# MachChoCaAn.net
KiCad netlist of a schematic drawn in Altium Designer
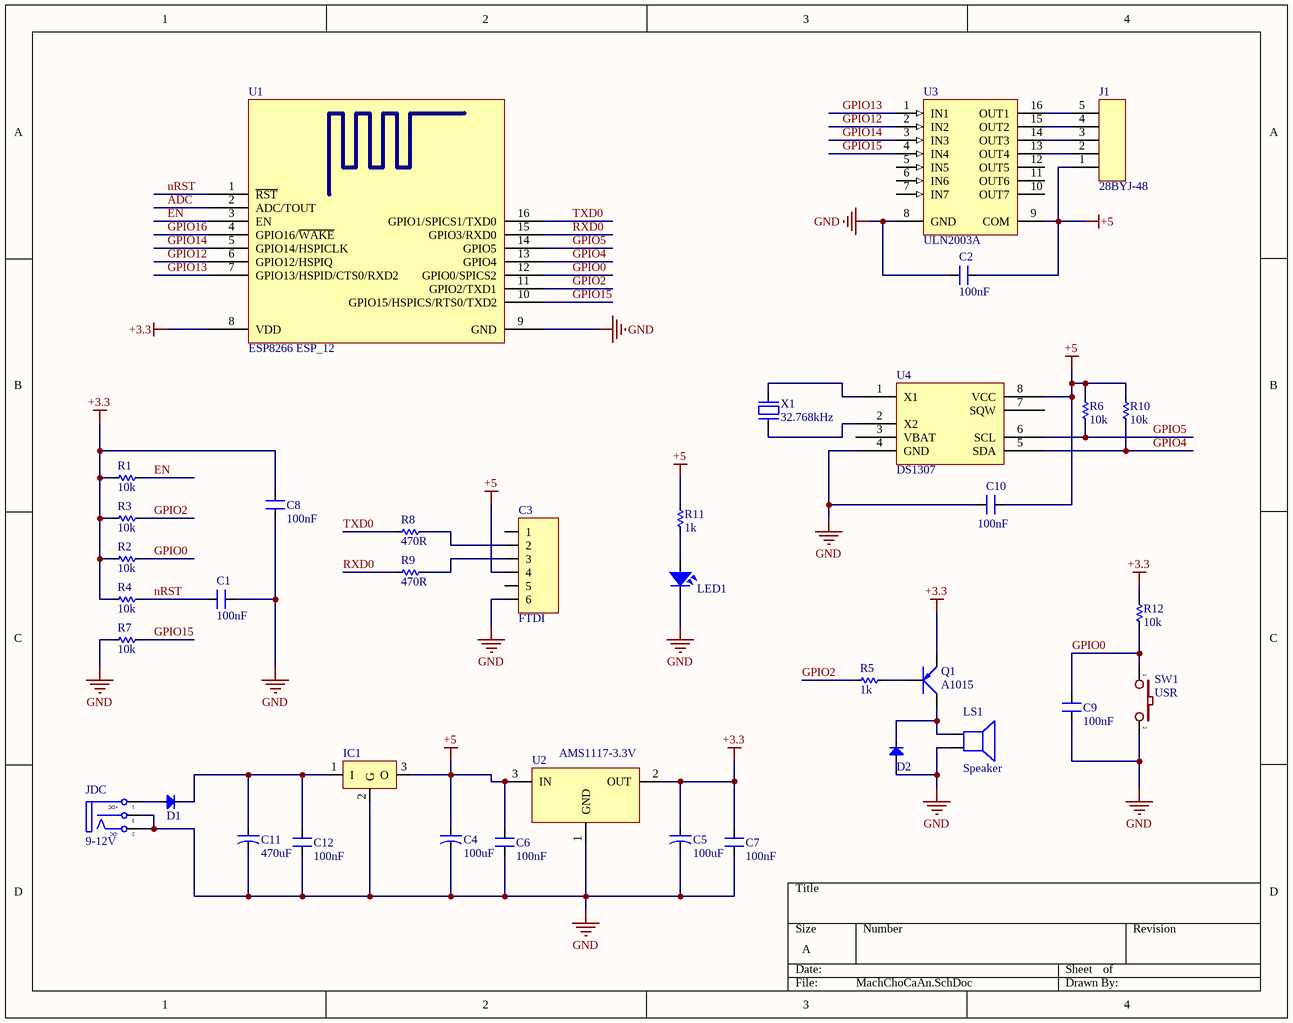
[diagram p0: MachChoCaAn.SchDoc]

(export (version "E")
  (design (tool "Eeschema 10.0.6"))
  (components
    (comp (ref "C1") (value "100nF") (footprint "CN-SMD-0805") (libsource (lib "LIBRARY") (part "CN")))
    (comp (ref "C2") (value "100nF") (footprint "CN-SMD-0805") (libsource (lib "LIBRARY") (part "CN")))
    (comp (ref "C3")
      (value "FTDI")
      (footprint "JP6-D1T")
      (description "WR-PHD 2.54 mm Angled Socket Header")
      (fields
        (field (name "MANUFACTURER") "Würth Elektronik eiSos GmbH")
        (field (name "PARTNO") "613006143121")
        (field (name "CREATED BY") "Karrer Zheng")
      )
      (libsource (lib "LIBRARY") (part "JP6"))
    )
    (comp (ref "C4")
      (value "100uF")
      (footprint "CA-ALU-6.3")
      (description "Capacitor (Semiconductor SIM Model)")
      (fields (field (name "PUBLISHER") "Altium Limited"))
      (libsource (lib "LIBRARY") (part "CN-ALU-DIP"))
    )
    (comp (ref "C5")
      (value "100uF")
      (footprint "CA-ALU-6.3")
      (description "Capacitor (Semiconductor SIM Model)")
      (fields (field (name "PUBLISHER") "Altium Limited"))
      (libsource (lib "LIBRARY") (part "CN-ALU-DIP"))
    )
    (comp (ref "C6") (value "100nF") (footprint "CN-SMD-0805") (libsource (lib "LIBRARY") (part "CN")))
    (comp (ref "C7") (value "100nF") (footprint "CN-SMD-0805") (libsource (lib "LIBRARY") (part "CN")))
    (comp (ref "C8") (value "100nF") (footprint "CN-SMD-0805") (libsource (lib "LIBRARY") (part "CN")))
    (comp (ref "C9") (value "100nF") (footprint "CN-SMD-0805") (libsource (lib "LIBRARY") (part "CN")))
    (comp (ref "C10") (value "100nF") (footprint "CN-SMD-0805") (libsource (lib "LIBRARY") (part "CN")))
    (comp (ref "C11")
      (value "470uF")
      (footprint "CA-ALU-10RL")
      (description "Capacitor (Semiconductor SIM Model)")
      (fields (field (name "PUBLISHER") "Altium Limited"))
      (libsource (lib "LIBRARY") (part "CN-ALU-DIP"))
    )
    (comp (ref "C12") (value "100nF") (footprint "CN-SMD-0805") (libsource (lib "LIBRARY") (part "CN")))
    (comp (ref "D1")
      (value "Diode SMD")
      (footprint "DIO-SMD-106")
      (description "Default Diode")
      (fields (field (name "PUBLISHER") "Altium Limited"))
      (libsource (lib "LIBRARY") (part "Diode SMD"))
    )
    (comp (ref "D2")
      (value "Diode SMD")
      (footprint "DIO-SMD-106")
      (description "Default Diode")
      (fields (field (name "PUBLISHER") "Altium Limited"))
      (libsource (lib "LIBRARY") (part "Diode SMD"))
    )
    (comp (ref "IC1")
      (value "LM78xx")
      (footprint "TO252-123")
      (description "Positive Voltage Regulator")
      (fields (field (name "PUBLISHER") "Altium Limited"))
      (libsource (lib "LIBRARY") (part "LM78xx"))
    )
    (comp (ref "J1") (value "28BYJ-48") (footprint "XH2.54-5P") (libsource (lib "User") (part "XH2.54-5P")))
    (comp (ref "JDC")
      (value "9-12V")
      (footprint "DC0")
      (description "Jac DC input")
      (libsource (lib "LIBRARY") (part "DCIN"))
    )
    (comp (ref "LED1")
      (value "PWR")
      (footprint "LED-0805-Orange")
      (libsource (lib "LIBRARY") (part "LED SMD"))
    )
    (comp (ref "LS1")
      (value "Speaker")
      (footprint "SPEAKER")
      (description "Loudspeaker")
      (fields (field (name "PUBLISHER") "Altium Limited"))
      (libsource (lib "LIBRARY") (part "Speaker"))
    )
    (comp (ref "Q1")
      (value "A1015")
      (footprint "SOT23B")
      (description "Dán")
      (libsource (lib "THU VIEN SCH_04042017_1") (part "A1015"))
    )
    (comp (ref "R1")
      (value "10k")
      (footprint "RES-SMD-0805")
      (description "Resistor")
      (fields
        (field (name "MANUFACTURER") "Generic Components")
        (field (name "PUBLISHER") "Altium Hobart Technology Centre")
      )
      (libsource (lib "LIBRARY") (part "Res-SMD"))
    )
    (comp (ref "R2")
      (value "10k")
      (footprint "RES-SMD-0805")
      (description "Resistor")
      (fields
        (field (name "MANUFACTURER") "Generic Components")
        (field (name "PUBLISHER") "Altium Hobart Technology Centre")
      )
      (libsource (lib "LIBRARY") (part "Res-SMD"))
    )
    (comp (ref "R3")
      (value "10k")
      (footprint "RES-SMD-0805")
      (description "Resistor")
      (fields
        (field (name "MANUFACTURER") "Generic Components")
        (field (name "PUBLISHER") "Altium Hobart Technology Centre")
      )
      (libsource (lib "LIBRARY") (part "Res-SMD"))
    )
    (comp (ref "R4")
      (value "10k")
      (footprint "RES-SMD-0805")
      (description "Resistor")
      (fields
        (field (name "MANUFACTURER") "Generic Components")
        (field (name "PUBLISHER") "Altium Hobart Technology Centre")
      )
      (libsource (lib "LIBRARY") (part "Res-SMD"))
    )
    (comp (ref "R5")
      (value "1k")
      (footprint "RES-SMD-0805")
      (description "Resistor")
      (fields
        (field (name "MANUFACTURER") "Generic Components")
        (field (name "PUBLISHER") "Altium Hobart Technology Centre")
      )
      (libsource (lib "LIBRARY") (part "Res-SMD"))
    )
    (comp (ref "R6")
      (value "10k")
      (footprint "RES-SMD-0805")
      (description "Resistor")
      (fields
        (field (name "MANUFACTURER") "Generic Components")
        (field (name "PUBLISHER") "Altium Hobart Technology Centre")
      )
      (libsource (lib "LIBRARY") (part "Res-SMD"))
    )
    (comp (ref "R7")
      (value "10k")
      (footprint "RES-SMD-0805")
      (description "Resistor")
      (fields
        (field (name "MANUFACTURER") "Generic Components")
        (field (name "PUBLISHER") "Altium Hobart Technology Centre")
      )
      (libsource (lib "LIBRARY") (part "Res-SMD"))
    )
    (comp (ref "R8")
      (value "470R")
      (footprint "RES-SMD-0805")
      (description "Resistor")
      (fields
        (field (name "MANUFACTURER") "Generic Components")
        (field (name "PUBLISHER") "Altium Hobart Technology Centre")
      )
      (libsource (lib "LIBRARY") (part "Res-SMD"))
    )
    (comp (ref "R9")
      (value "470R")
      (footprint "RES-SMD-0805")
      (description "Resistor")
      (fields
        (field (name "MANUFACTURER") "Generic Components")
        (field (name "PUBLISHER") "Altium Hobart Technology Centre")
      )
      (libsource (lib "LIBRARY") (part "Res-SMD"))
    )
    (comp (ref "R10")
      (value "10k")
      (footprint "RES-SMD-0805")
      (description "Resistor")
      (fields
        (field (name "MANUFACTURER") "Generic Components")
        (field (name "PUBLISHER") "Altium Hobart Technology Centre")
      )
      (libsource (lib "LIBRARY") (part "Res-SMD"))
    )
    (comp (ref "R11")
      (value "1k")
      (footprint "RES-SMD-0805")
      (description "Resistor")
      (fields
        (field (name "MANUFACTURER") "Generic Components")
        (field (name "PUBLISHER") "Altium Hobart Technology Centre")
      )
      (libsource (lib "LIBRARY") (part "Res-SMD"))
    )
    (comp (ref "R12")
      (value "10k")
      (footprint "RES-SMD-0805")
      (description "Resistor")
      (fields
        (field (name "MANUFACTURER") "Generic Components")
        (field (name "PUBLISHER") "Altium Hobart Technology Centre")
      )
      (libsource (lib "LIBRARY") (part "Res-SMD"))
    )
    (comp (ref "SW1")
      (value "USR")
      (footprint "SW1-DIP")
      (description "Switch button 2 pin")
      (libsource (lib "LIBRARY") (part "SW2"))
    )
    (comp (ref "U1")
      (value "ESP8266 ESP_12")
      (footprint "ESP8266 ESP_12")
      (description "ESP8266 ESP-12")
      (fields (field (name "PUBLISHER") "Cynetik Group") (field (name "LATESTREVIEWER") "Zion Blue"))
      (libsource (lib "ESP8266") (part "ESP8266 ESP_12"))
    )
    (comp (ref "U2")
      (value "AMS1117-3.3V")
      (footprint "SOT223")
      (description "800mA Low-Dropout Linear Regulator")
      (fields (field (name "CREATOR") "Nguyen Ba Bien"))
      (libsource (lib "LIBRARY") (part "LM1117"))
    )
    (comp (ref "U3")
      (value "ULN2003A")
      (footprint "SO16")
      (description "High-Voltage, High-Current Darlington Array")
      (fields (field (name "PUBLISHER") "Altium Limited"))
      (libsource (lib "LIBRARY") (part "ULN2003A"))
    )
    (comp (ref "U4") (value "DS1307") (footprint "DS1307") (libsource (lib "User") (part "DS1307")))
    (comp (ref "X1")
      (value "32.768kHz")
      (footprint "XT32k")
      (description "Crystal, 32.768 KHz, -40 to 85 degC, 3.2 x 1.5 x 0.9 mm SMD")
      (libsource (lib "LIBRARY") (part "XT2"))
    )
  )
  (nets
    (net (code "1") (name "+3.3") (class "Default")
      (node (ref "C5") (pin "1") (pinfunction "1_1") (pintype "passive"))
      (node (ref "C7") (pin "2") (pinfunction "2_2") (pintype "passive"))
      (node (ref "C8") (pin "2") (pinfunction "2_2") (pintype "passive"))
      (node (ref "Q1") (pin "3") (pinfunction "E_3") (pintype "passive"))
      (node (ref "R1") (pin "1") (pinfunction "1_1") (pintype "passive"))
      (node (ref "R12") (pin "2") (pinfunction "2_2") (pintype "passive"))
      (node (ref "R2") (pin "1") (pinfunction "1_1") (pintype "passive"))
      (node (ref "R3") (pin "1") (pinfunction "1_1") (pintype "passive"))
      (node (ref "R4") (pin "1") (pinfunction "1_1") (pintype "passive"))
      (node (ref "U1") (pin "8") (pinfunction "VDD_8") (pintype "passive"))
      (node (ref "U2") (pin "2") (pinfunction "OUT_2") (pintype "passive"))
    )
    (net (code "2") (name "+5") (class "Default")
      (node (ref "C10") (pin "2") (pinfunction "2_2") (pintype "passive"))
      (node (ref "C2") (pin "2") (pinfunction "2_2") (pintype "passive"))
      (node (ref "C3") (pin "4") (pinfunction "4_4") (pintype "passive"))
      (node (ref "C4") (pin "1") (pinfunction "1_1") (pintype "passive"))
      (node (ref "C6") (pin "2") (pinfunction "2_2") (pintype "passive"))
      (node (ref "IC1") (pin "3") (pinfunction "O_3") (pintype "power_in"))
      (node (ref "J1") (pin "1") (pinfunction "1_1") (pintype "passive"))
      (node (ref "R10") (pin "2") (pinfunction "2_2") (pintype "passive"))
      (node (ref "R11") (pin "1") (pinfunction "1_1") (pintype "passive"))
      (node (ref "R6") (pin "2") (pinfunction "2_2") (pintype "passive"))
      (node (ref "U2") (pin "3") (pinfunction "IN_3") (pintype "passive"))
      (node (ref "U3") (pin "9") (pinfunction "COM_9") (pintype "passive"))
      (node (ref "U4") (pin "8") (pinfunction "VCC_8") (pintype "passive"))
    )
    (net (code "3") (name "/ADC") (class "Default")
      (node (ref "U1") (pin "2") (pinfunction "ADC/TOUT_2") (pintype "passive"))
    )
    (net (code "4") (name "/EN") (class "Default")
      (node (ref "R1") (pin "2") (pinfunction "2_2") (pintype "passive"))
      (node (ref "U1") (pin "3") (pinfunction "EN_3") (pintype "passive"))
    )
    (net (code "5") (name "/GPIO0") (class "Default")
      (node (ref "C9") (pin "2") (pinfunction "2_2") (pintype "passive"))
      (node (ref "R12") (pin "1") (pinfunction "1_1") (pintype "passive"))
      (node (ref "R2") (pin "2") (pinfunction "2_2") (pintype "passive"))
      (node (ref "SW1") (pin "1") (pinfunction "1_1") (pintype "passive"))
      (node (ref "U1") (pin "12") (pinfunction "GPIO0/SPICS2_12") (pintype "passive"))
    )
    (net (code "6") (name "/GPIO2") (class "Default")
      (node (ref "R3") (pin "2") (pinfunction "2_2") (pintype "passive"))
      (node (ref "R5") (pin "2") (pinfunction "2_2") (pintype "passive"))
      (node (ref "U1") (pin "11") (pinfunction "GPIO2/TXD1_11") (pintype "passive"))
    )
    (net (code "7") (name "/GPIO4") (class "Default")
      (node (ref "R10") (pin "1") (pinfunction "1_1") (pintype "passive"))
      (node (ref "U1") (pin "13") (pinfunction "GPIO4_13") (pintype "passive"))
      (node (ref "U4") (pin "5") (pinfunction "SDA_5") (pintype "passive"))
    )
    (net (code "8") (name "/GPIO5") (class "Default")
      (node (ref "R6") (pin "1") (pinfunction "1_1") (pintype "passive"))
      (node (ref "U1") (pin "14") (pinfunction "GPIO5_14") (pintype "passive"))
      (node (ref "U4") (pin "6") (pinfunction "SCL_6") (pintype "passive"))
    )
    (net (code "9") (name "/GPIO12") (class "Default")
      (node (ref "U1") (pin "6") (pinfunction "GPIO12/HSPIQ_6") (pintype "passive"))
      (node (ref "U3") (pin "2") (pinfunction "IN2_2") (pintype "input"))
    )
    (net (code "10") (name "/GPIO13") (class "Default")
      (node (ref "U1") (pin "7") (pinfunction "GPIO13/HSPID/CTS0/RXD2_7") (pintype "passive"))
      (node (ref "U3") (pin "1") (pinfunction "IN1_1") (pintype "input"))
    )
    (net (code "11") (name "/GPIO14") (class "Default")
      (node (ref "U1") (pin "5") (pinfunction "GPIO14/HSPICLK_5") (pintype "passive"))
      (node (ref "U3") (pin "3") (pinfunction "IN3_3") (pintype "input"))
    )
    (net (code "12") (name "/GPIO15") (class "Default")
      (node (ref "R7") (pin "2") (pinfunction "2_2") (pintype "passive"))
      (node (ref "U1") (pin "10") (pinfunction "GPIO15/HSPICS/RTS0/TXD2_10") (pintype "passive"))
      (node (ref "U3") (pin "4") (pinfunction "IN4_4") (pintype "input"))
    )
    (net (code "13") (name "/GPIO16") (class "Default")
      (node (ref "U1") (pin "4") (pinfunction "GPIO16/~{WAKE}_4") (pintype "passive"))
    )
    (net (code "14") (name "/RXD0") (class "Default")
      (node (ref "R9") (pin "1") (pinfunction "1_1") (pintype "passive"))
      (node (ref "U1") (pin "15") (pinfunction "GPIO3/RXD0_15") (pintype "passive"))
    )
    (net (code "15") (name "/TXD0") (class "Default")
      (node (ref "R8") (pin "1") (pinfunction "1_1") (pintype "passive"))
      (node (ref "U1") (pin "16") (pinfunction "GPIO1/SPICS1/TXD0_16") (pintype "passive"))
    )
    (net (code "16") (name "/nRST") (class "Default")
      (node (ref "C1") (pin "1") (pinfunction "1_1") (pintype "passive"))
      (node (ref "R4") (pin "2") (pinfunction "2_2") (pintype "passive"))
      (node (ref "U1") (pin "1") (pinfunction "~{RST}_1") (pintype "passive"))
    )
    (net (code "17") (name "GND") (class "Default")
      (node (ref "C1") (pin "2") (pinfunction "2_2") (pintype "passive"))
      (node (ref "C10") (pin "1") (pinfunction "1_1") (pintype "passive"))
      (node (ref "C11") (pin "2") (pinfunction "2_2") (pintype "passive"))
      (node (ref "C12") (pin "1") (pinfunction "1_1") (pintype "passive"))
      (node (ref "C2") (pin "1") (pinfunction "1_1") (pintype "passive"))
      (node (ref "C3") (pin "6") (pinfunction "6_6") (pintype "passive"))
      (node (ref "C4") (pin "2") (pinfunction "2_2") (pintype "passive"))
      (node (ref "C5") (pin "2") (pinfunction "2_2") (pintype "passive"))
      (node (ref "C6") (pin "1") (pinfunction "1_1") (pintype "passive"))
      (node (ref "C7") (pin "1") (pinfunction "1_1") (pintype "passive"))
      (node (ref "C8") (pin "1") (pinfunction "1_1") (pintype "passive"))
      (node (ref "C9") (pin "1") (pinfunction "1_1") (pintype "passive"))
      (node (ref "D2") (pin "1") (pinfunction "A_1") (pintype "passive"))
      (node (ref "IC1") (pin "2") (pinfunction "G_2") (pintype "power_in"))
      (node (ref "JDC") (pin "2") (pinfunction "TN_2") (pintype "passive"))
      (node (ref "JDC") (pin "3") (pinfunction "S_3") (pintype "power_in"))
      (node (ref "LED1") (pin "2") (pinfunction "2_2") (pintype "passive"))
      (node (ref "LS1") (pin "2") (pinfunction "2_2") (pintype "passive"))
      (node (ref "R7") (pin "1") (pinfunction "1_1") (pintype "passive"))
      (node (ref "SW1") (pin "2") (pinfunction "2_2") (pintype "passive"))
      (node (ref "U1") (pin "9") (pinfunction "GND_9") (pintype "passive"))
      (node (ref "U2") (pin "1") (pinfunction "GND_1") (pintype "passive"))
      (node (ref "U3") (pin "8") (pinfunction "GND_8") (pintype "power_in"))
      (node (ref "U4") (pin "4") (pinfunction "GND_4") (pintype "passive"))
    )
    (net (code "18") (name "Net-(C3-Pad2)") (class "Default")
      (node (ref "C3") (pin "2") (pinfunction "2_2") (pintype "passive"))
      (node (ref "R8") (pin "2") (pinfunction "2_2") (pintype "passive"))
    )
    (net (code "19") (name "Net-(C3-Pad3)") (class "Default")
      (node (ref "C3") (pin "3") (pinfunction "3_3") (pintype "passive"))
      (node (ref "R9") (pin "2") (pinfunction "2_2") (pintype "passive"))
    )
    (net (code "20") (name "Net-(D1-A)") (class "Default")
      (node (ref "D1") (pin "1") (pinfunction "A_1") (pintype "passive"))
      (node (ref "JDC") (pin "1") (pinfunction "T_1") (pintype "passive"))
    )
    (net (code "21") (name "Net-(D1-K)") (class "Default")
      (node (ref "C11") (pin "1") (pinfunction "1_1") (pintype "passive"))
      (node (ref "C12") (pin "2") (pinfunction "2_2") (pintype "passive"))
      (node (ref "D1") (pin "2") (pinfunction "K_2") (pintype "passive"))
      (node (ref "IC1") (pin "1") (pinfunction "I_1") (pintype "power_in"))
    )
    (net (code "22") (name "Net-(D2-K)") (class "Default")
      (node (ref "D2") (pin "2") (pinfunction "K_2") (pintype "passive"))
      (node (ref "LS1") (pin "1") (pinfunction "1_1") (pintype "passive"))
      (node (ref "Q1") (pin "2") (pinfunction "C_2") (pintype "passive"))
    )
    (net (code "23") (name "Net-(LED1-Pad1)") (class "Default")
      (node (ref "LED1") (pin "1") (pinfunction "1_1") (pintype "passive"))
      (node (ref "R11") (pin "2") (pinfunction "2_2") (pintype "passive"))
    )
    (net (code "24") (name "Net-(Q1-B)") (class "Default")
      (node (ref "Q1") (pin "1") (pinfunction "B_1") (pintype "passive"))
      (node (ref "R5") (pin "1") (pinfunction "1_1") (pintype "passive"))
    )
    (net (code "25") (name "Net-(U3-OUT1)") (class "Default")
      (node (ref "J1") (pin "5") (pinfunction "5_5") (pintype "passive"))
      (node (ref "U3") (pin "16") (pinfunction "OUT1_16") (pintype "open_collector"))
    )
    (net (code "26") (name "Net-(U3-OUT2)") (class "Default")
      (node (ref "J1") (pin "4") (pinfunction "4_4") (pintype "passive"))
      (node (ref "U3") (pin "15") (pinfunction "OUT2_15") (pintype "open_collector"))
    )
    (net (code "27") (name "Net-(U3-OUT3)") (class "Default")
      (node (ref "J1") (pin "3") (pinfunction "3_3") (pintype "passive"))
      (node (ref "U3") (pin "14") (pinfunction "OUT3_14") (pintype "open_collector"))
    )
    (net (code "28") (name "Net-(U3-OUT4)") (class "Default")
      (node (ref "J1") (pin "2") (pinfunction "2_2") (pintype "passive"))
      (node (ref "U3") (pin "13") (pinfunction "OUT4_13") (pintype "open_collector"))
    )
    (net (code "29") (name "Net-(U4-X1)") (class "Default")
      (node (ref "U4") (pin "1") (pinfunction "X1_1") (pintype "passive"))
      (node (ref "X1") (pin "2") (pinfunction "2_2") (pintype "passive"))
    )
    (net (code "30") (name "Net-(U4-X2)") (class "Default")
      (node (ref "U4") (pin "2") (pinfunction "X2_2") (pintype "passive"))
      (node (ref "X1") (pin "1") (pinfunction "1_1") (pintype "passive"))
    )
    (net (code "31") (name "unconnected-(C3-Pad1)") (class "Default")
      (node (ref "C3") (pin "1") (pinfunction "1_1") (pintype "passive"))
    )
    (net (code "32") (name "unconnected-(C3-Pad5)") (class "Default")
      (node (ref "C3") (pin "5") (pinfunction "5_5") (pintype "passive"))
    )
    (net (code "33") (name "unconnected-(U3-IN5-Pad5)") (class "Default")
      (node (ref "U3") (pin "5") (pinfunction "IN5_5") (pintype "input"))
    )
    (net (code "34") (name "unconnected-(U3-IN6-Pad6)") (class "Default")
      (node (ref "U3") (pin "6") (pinfunction "IN6_6") (pintype "input"))
    )
    (net (code "35") (name "unconnected-(U3-IN7-Pad7)") (class "Default")
      (node (ref "U3") (pin "7") (pinfunction "IN7_7") (pintype "input"))
    )
    (net (code "36") (name "unconnected-(U3-OUT5-Pad12)") (class "Default")
      (node (ref "U3") (pin "12") (pinfunction "OUT5_12") (pintype "open_collector"))
    )
    (net (code "37") (name "unconnected-(U3-OUT6-Pad11)") (class "Default")
      (node (ref "U3") (pin "11") (pinfunction "OUT6_11") (pintype "open_collector"))
    )
    (net (code "38") (name "unconnected-(U3-OUT7-Pad10)") (class "Default")
      (node (ref "U3") (pin "10") (pinfunction "OUT7_10") (pintype "open_collector"))
    )
    (net (code "39") (name "unconnected-(U4-SQW-Pad7)") (class "Default")
      (node (ref "U4") (pin "7") (pinfunction "SQW_7") (pintype "passive"))
    )
    (net (code "40") (name "unconnected-(U4-VBAT-Pad3)") (class "Default")
      (node (ref "U4") (pin "3") (pinfunction "VBAT_3") (pintype "passive"))
    )
  )
)
